# main.net
KiCad netlist of a schematic drawn in Altium Designer
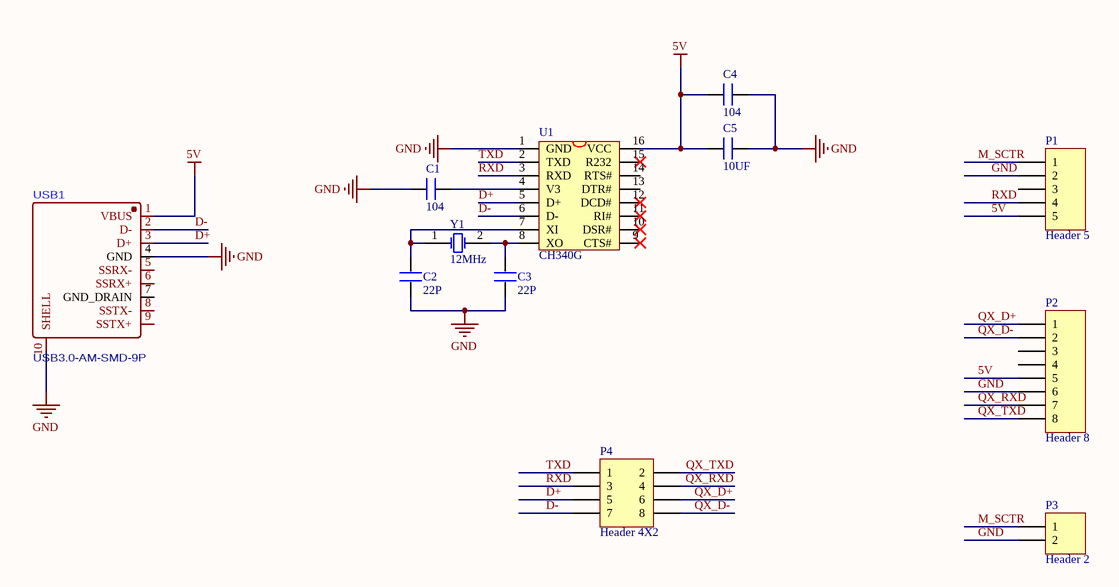
[diagram p0: main.SchDoc]

(export (version "E")
  (design (tool "Eeschema 10.0.6"))
  (components
    (comp (ref "C1") (value "104") (footprint "R0603") (libsource (lib "Explorer STM32F407封装库") (part "C")))
    (comp (ref "C2") (value "22P") (footprint "R0603") (libsource (lib "Explorer STM32F407封装库") (part "C")))
    (comp (ref "C3") (value "22P") (footprint "R0603") (libsource (lib "Explorer STM32F407封装库") (part "C")))
    (comp (ref "C4") (value "104") (footprint "R0603") (libsource (lib "Explorer STM32F407封装库") (part "C")))
    (comp (ref "C5") (value "10UF") (footprint "R0603") (libsource (lib "Explorer STM32F407封装库") (part "C")))
    (comp (ref "P1")
      (value "Header 5")
      (footprint "PH2.0-5PWB")
      (description "Header, 5-Pin")
      (fields (field (name "PUBLISHER") "Altium Limited"))
      (libsource (lib "Miscellaneous Connectors") (part "Header 5"))
    )
    (comp (ref "P2")
      (value "Header 8")
      (footprint "CONN-SMD_X2016WRS-08-9TSW")
      (description "Header, 8-Pin")
      (fields (field (name "PUBLISHER") "Altium Limited"))
      (libsource (lib "Miscellaneous Connectors") (part "Header 8"))
    )
    (comp (ref "P3")
      (value "Header 2")
      (footprint "HDR1X2")
      (description "Header, 2-Pin")
      (fields (field (name "PUBLISHER") "Altium Limited"))
      (libsource (lib "Miscellaneous Connectors") (part "Header 2"))
    )
    (comp (ref "P4")
      (value "Header 4X2")
      (footprint "HDR2X4")
      (description "Header, 4-Pin, Dual row")
      (fields (field (name "PUBLISHER") "Altium Limited"))
      (libsource (lib "Miscellaneous Connectors") (part "Header 4X2"))
    )
    (comp (ref "U1")
      (value "CH340G")
      (footprint "SOIC-16_L9.9-W3.9-P1.27-LS6.0-BL")
      (description "USB2UART")
      (libsource (lib "Explorer STM32F407封装库") (part "CH340G"))
    )
    (comp (ref "USB1")
      (value "USB3.0-AM-SMD-9P")
      (footprint "USB3.0-AM-SMD-9P")
      (libsource (lib "USB3.0-AM-SMD-9P_2021-11-30") (part "USB3.0-AM-SMD-9P"))
    )
    (comp (ref "Y1")
      (value "12MHz")
      (footprint "OSC-SMD_L11.4-W4.5-LS12.5")
      (description "Crystal Oscillator")
      (fields (field (name "PUBLISHER") "Altium Limited"))
      (libsource (lib "Explorer STM32F407封装库") (part "XTAL"))
    )
  )
  (nets
    (net (code "1") (name "/D+") (class "Default")
      (node (ref "P4") (pin "5") (pinfunction "5_5") (pintype "passive"))
      (node (ref "U1") (pin "5") (pinfunction "D+_5") (pintype "passive"))
      (node (ref "USB1") (pin "3") (pinfunction "D+_3") (pintype "passive"))
    )
    (net (code "2") (name "/D-") (class "Default")
      (node (ref "P4") (pin "7") (pinfunction "7_7") (pintype "passive"))
      (node (ref "U1") (pin "6") (pinfunction "D-_6") (pintype "passive"))
      (node (ref "USB1") (pin "2") (pinfunction "D-_2") (pintype "passive"))
    )
    (net (code "3") (name "/M_SCTR") (class "Default")
      (node (ref "P1") (pin "1") (pinfunction "1_1") (pintype "passive"))
      (node (ref "P3") (pin "1") (pinfunction "1_1") (pintype "passive"))
    )
    (net (code "4") (name "/QX_D+") (class "Default")
      (node (ref "P2") (pin "1") (pinfunction "1_1") (pintype "passive"))
      (node (ref "P4") (pin "6") (pinfunction "6_6") (pintype "passive"))
    )
    (net (code "5") (name "/QX_D-") (class "Default")
      (node (ref "P2") (pin "2") (pinfunction "2_2") (pintype "passive"))
      (node (ref "P4") (pin "8") (pinfunction "8_8") (pintype "passive"))
    )
    (net (code "6") (name "/QX_RXD") (class "Default")
      (node (ref "P2") (pin "7") (pinfunction "7_7") (pintype "passive"))
      (node (ref "P4") (pin "4") (pinfunction "4_4") (pintype "passive"))
    )
    (net (code "7") (name "/QX_TXD") (class "Default")
      (node (ref "P2") (pin "8") (pinfunction "8_8") (pintype "passive"))
      (node (ref "P4") (pin "2") (pinfunction "2_2") (pintype "passive"))
    )
    (net (code "8") (name "/RXD") (class "Default")
      (node (ref "P1") (pin "4") (pinfunction "4_4") (pintype "passive"))
      (node (ref "P4") (pin "3") (pinfunction "3_3") (pintype "passive"))
      (node (ref "U1") (pin "3") (pinfunction "RXD_3") (pintype "passive"))
    )
    (net (code "9") (name "/TXD") (class "Default")
      (node (ref "P4") (pin "1") (pinfunction "1_1") (pintype "passive"))
      (node (ref "U1") (pin "2") (pinfunction "TXD_2") (pintype "passive"))
    )
    (net (code "10") (name "5V") (class "Default")
      (node (ref "C4") (pin "2") (pintype "passive"))
      (node (ref "C5") (pin "1") (pintype "passive"))
      (node (ref "P1") (pin "5") (pinfunction "5_5") (pintype "passive"))
      (node (ref "P2") (pin "5") (pinfunction "5_5") (pintype "passive"))
      (node (ref "U1") (pin "16") (pinfunction "VCC_16") (pintype "passive"))
      (node (ref "USB1") (pin "1") (pinfunction "VBUS_1") (pintype "passive"))
    )
    (net (code "11") (name "GND") (class "Default")
      (node (ref "C1") (pin "1") (pintype "passive"))
      (node (ref "C2") (pin "1") (pintype "passive"))
      (node (ref "C3") (pin "1") (pintype "passive"))
      (node (ref "C4") (pin "1") (pintype "passive"))
      (node (ref "C5") (pin "2") (pintype "passive"))
      (node (ref "P1") (pin "2") (pinfunction "2_2") (pintype "passive"))
      (node (ref "P2") (pin "6") (pinfunction "6_6") (pintype "passive"))
      (node (ref "P3") (pin "2") (pinfunction "2_2") (pintype "passive"))
      (node (ref "U1") (pin "1") (pinfunction "GND_1") (pintype "passive"))
      (node (ref "USB1") (pin "10") (pinfunction "SHELL_10") (pintype "passive"))
      (node (ref "USB1") (pin "4") (pinfunction "GND_4") (pintype "passive"))
    )
    (net (code "12") (name "Net-(U1-V3)") (class "Default")
      (node (ref "C1") (pin "2") (pintype "passive"))
      (node (ref "U1") (pin "4") (pinfunction "V3_4") (pintype "passive"))
    )
    (net (code "13") (name "Net-(U1-XI)") (class "Default")
      (node (ref "C2") (pin "2") (pintype "passive"))
      (node (ref "U1") (pin "7") (pinfunction "XI_7") (pintype "passive"))
      (node (ref "Y1") (pin "1") (pinfunction "OSC1_1") (pintype "passive"))
    )
    (net (code "14") (name "Net-(U1-XO)") (class "Default")
      (node (ref "C3") (pin "2") (pintype "passive"))
      (node (ref "U1") (pin "8") (pinfunction "XO_8") (pintype "passive"))
      (node (ref "Y1") (pin "2") (pinfunction "OSC2_2") (pintype "passive"))
    )
    (net (code "15") (name "unconnected-(P1-Pad3)") (class "Default")
      (node (ref "P1") (pin "3") (pinfunction "3_3") (pintype "passive"))
    )
    (net (code "16") (name "unconnected-(P2-Pad3)") (class "Default")
      (node (ref "P2") (pin "3") (pinfunction "3_3") (pintype "passive"))
    )
    (net (code "17") (name "unconnected-(P2-Pad4)") (class "Default")
      (node (ref "P2") (pin "4") (pinfunction "4_4") (pintype "passive"))
    )
    (net (code "18") (name "unconnected-(U1-CTS#-Pad9)") (class "Default")
      (node (ref "U1") (pin "9") (pinfunction "CTS#_9") (pintype "passive+no_connect"))
    )
    (net (code "19") (name "unconnected-(U1-DCD#-Pad12)") (class "Default")
      (node (ref "U1") (pin "12") (pinfunction "DCD#_12") (pintype "passive+no_connect"))
    )
    (net (code "20") (name "unconnected-(U1-DSR#-Pad10)") (class "Default")
      (node (ref "U1") (pin "10") (pinfunction "DSR#_10") (pintype "passive+no_connect"))
    )
    (net (code "21") (name "unconnected-(U1-DTR#-Pad13)") (class "Default")
      (node (ref "U1") (pin "13") (pinfunction "DTR#_13") (pintype "passive"))
    )
    (net (code "22") (name "unconnected-(U1-R232-Pad15)") (class "Default")
      (node (ref "U1") (pin "15") (pinfunction "R232_15") (pintype "passive+no_connect"))
    )
    (net (code "23") (name "unconnected-(U1-RI#-Pad11)") (class "Default")
      (node (ref "U1") (pin "11") (pinfunction "RI#_11") (pintype "passive+no_connect"))
    )
    (net (code "24") (name "unconnected-(U1-RTS#-Pad14)") (class "Default")
      (node (ref "U1") (pin "14") (pinfunction "RTS#_14") (pintype "passive"))
    )
    (net (code "25") (name "unconnected-(USB1-GND_DRAIN-Pad7)") (class "Default")
      (node (ref "USB1") (pin "7") (pinfunction "GND_DRAIN_7") (pintype "passive"))
    )
    (net (code "26") (name "unconnected-(USB1-SSRX+-Pad6)") (class "Default")
      (node (ref "USB1") (pin "6") (pinfunction "SSRX+_6") (pintype "passive"))
    )
    (net (code "27") (name "unconnected-(USB1-SSRX--Pad5)") (class "Default")
      (node (ref "USB1") (pin "5") (pinfunction "SSRX-_5") (pintype "passive"))
    )
    (net (code "28") (name "unconnected-(USB1-SSTX+-Pad9)") (class "Default")
      (node (ref "USB1") (pin "9") (pinfunction "SSTX+_9") (pintype "passive"))
    )
    (net (code "29") (name "unconnected-(USB1-SSTX--Pad8)") (class "Default")
      (node (ref "USB1") (pin "8") (pinfunction "SSTX-_8") (pintype "passive"))
    )
  )
)
